# Sec_Controller_Sheet1.net
KiCad netlist of a schematic drawn in Altium Designer
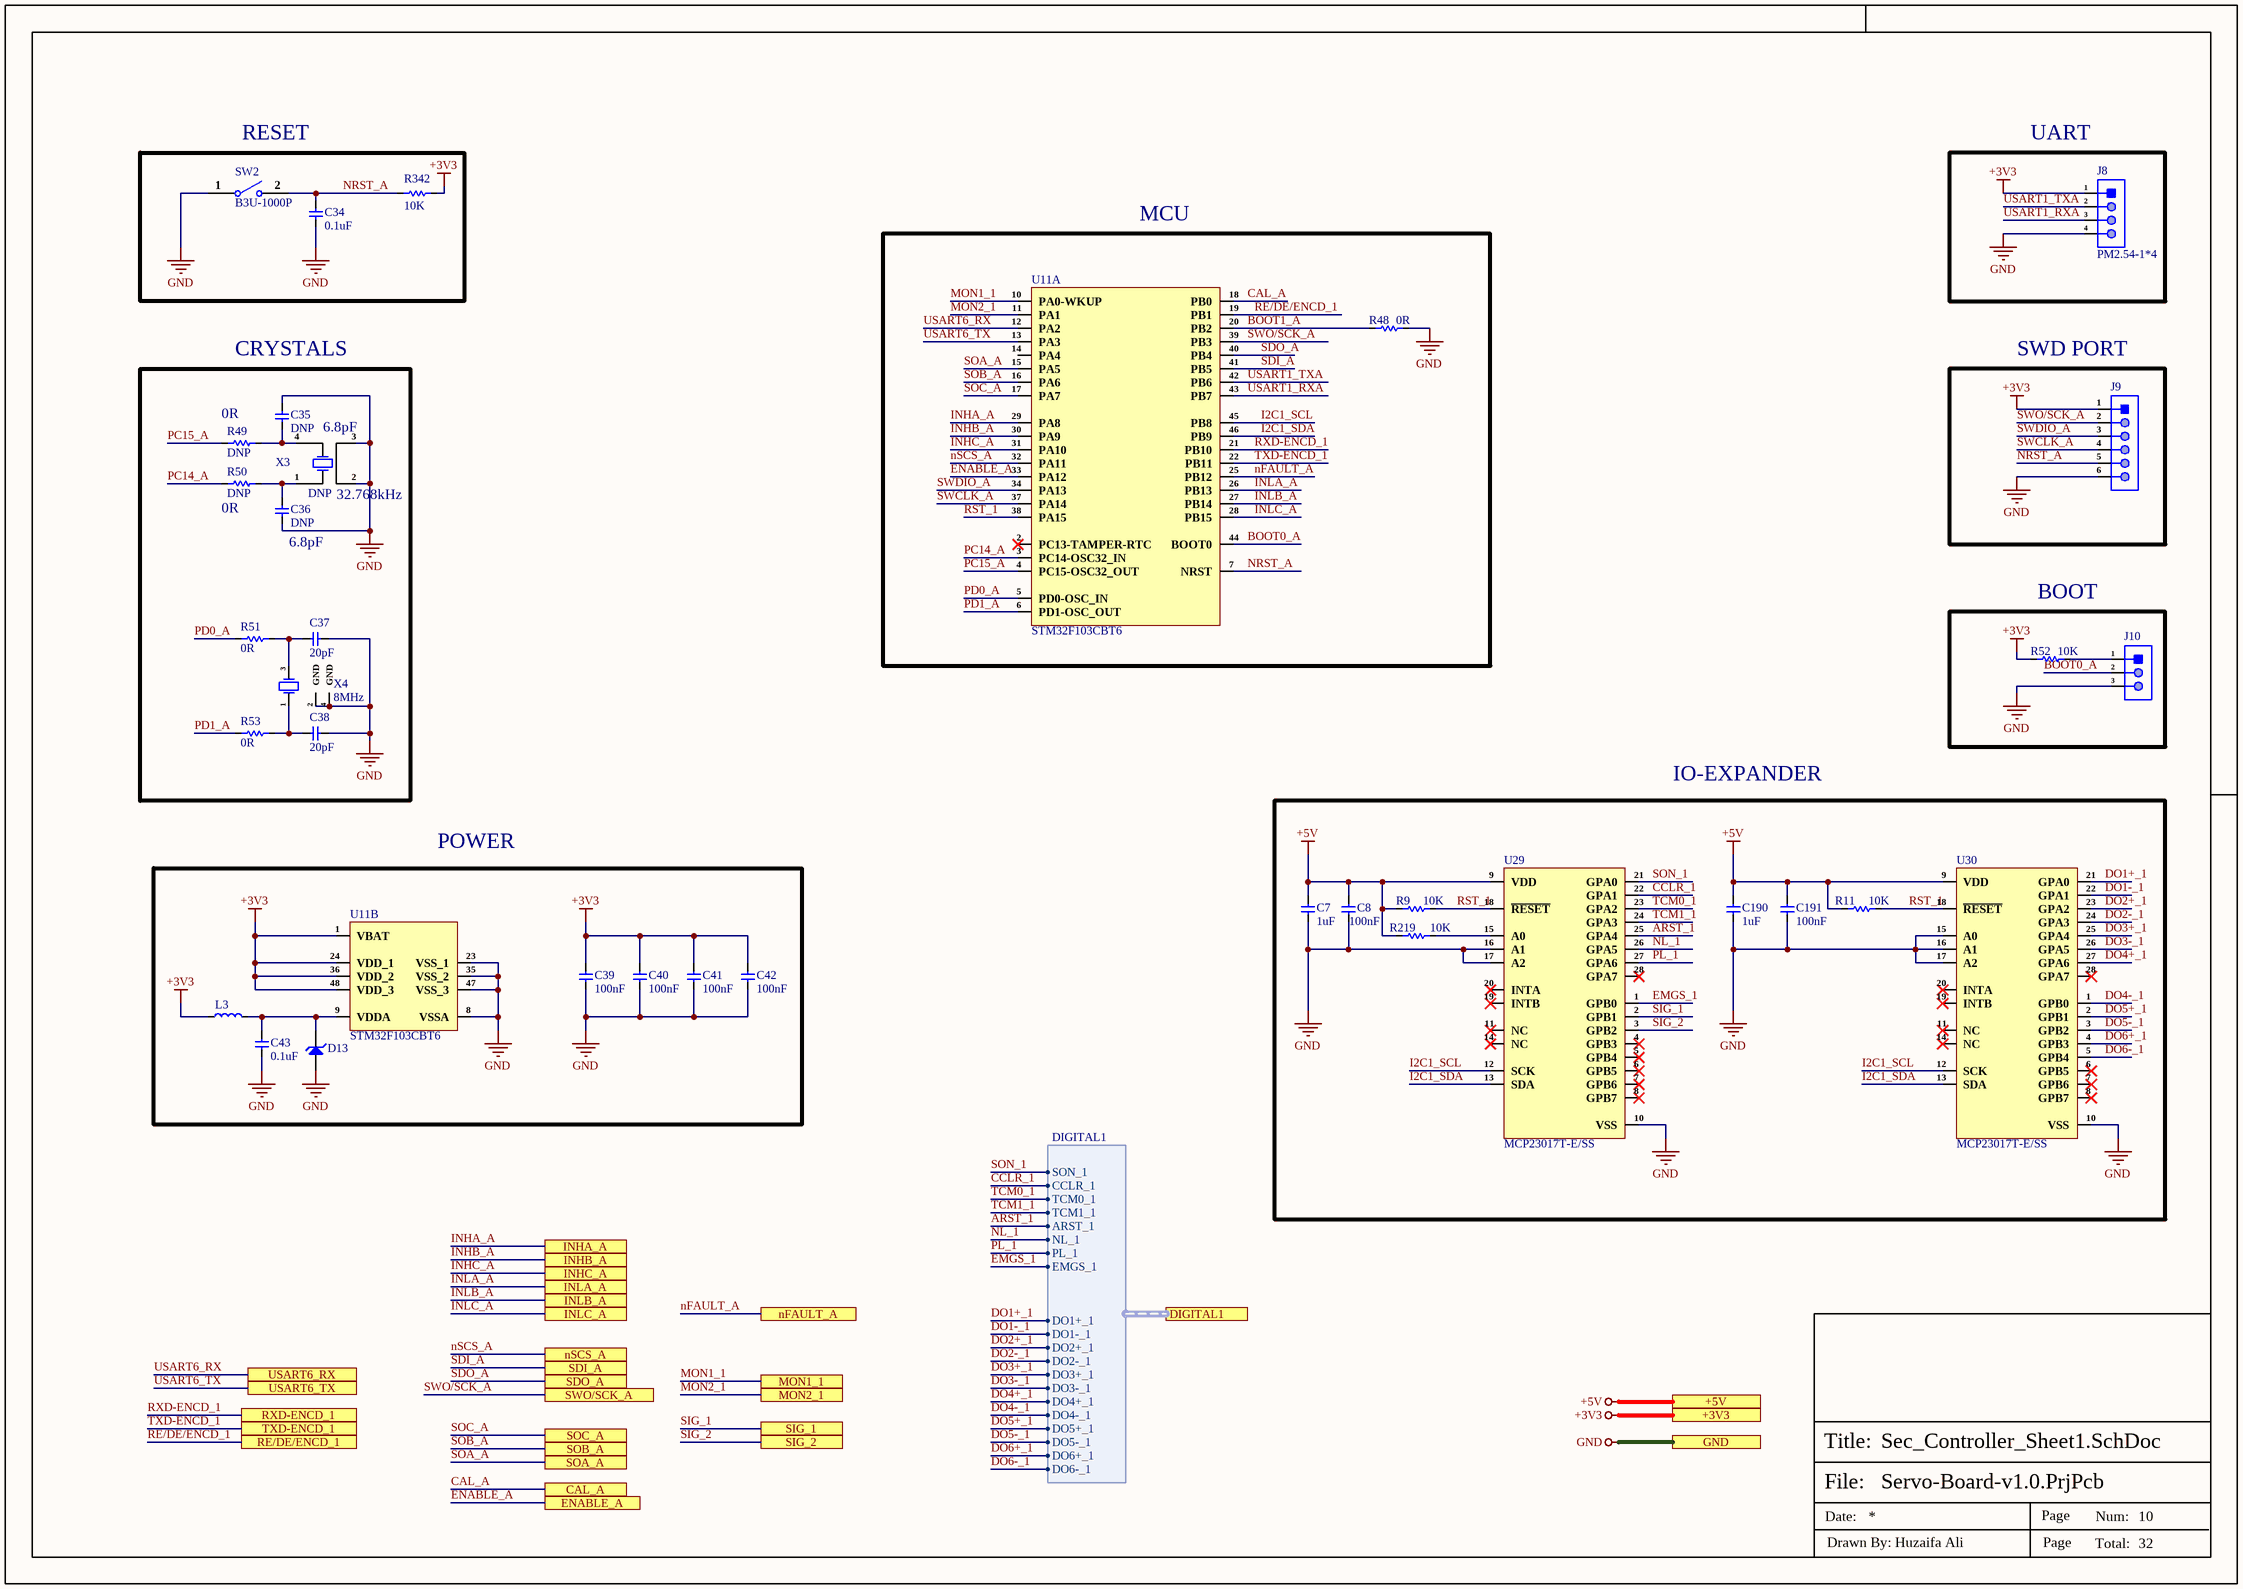
[diagram p0: Sec_Controller_Sheet1.SchDoc]

(export (version "E")
  (design (tool "Eeschema 10.0.6"))
  (components
    (comp (ref "C7")
      (value "1uF")
      (footprint "Cap-0402")
      (description "CAP CER 1UF 10V X5R 0402")
      (fields
        (field (name "MANUFACTURER") "Yageo")
        (field (name "MANUFACTURER PART NUMBER") "CC0402KRX5R6BB105")
      )
      (libsource (lib "eSpark Libraries") (part "CC0402KRX5R6BB105"))
    )
    (comp (ref "C8")
      (value "100nF")
      (footprint "cap-0402")
      (description "CAP CER 0.1UF 50V X7R 0402")
      (fields
        (field (name "MANUFACTURER") "TDK")
        (field (name "MANUFACTURER PART NUMBER") "C1005X7R1H104KT000F")
      )
      (libsource (lib "eSpark Libraries") (part "C1005X7R1H104KT000F"))
    )
    (comp (ref "C34")
      (value "0.1uF")
      (footprint "Cap-0402")
      (description "CAP CER 0.1UF 16V X7R 0402")
      (fields
        (field (name "MANUFACTURER") "Yageo")
        (field (name "MANUFACTURER PART NUMBER") "CC0402JRX7R7BB104")
      )
      (libsource (lib "eSpark Libraries") (part "CC0402JRX7R7BB104"))
    )
    (comp (ref "C35")
      (value "DNP")
      (footprint "Cap-0402")
      (description "CAP CER 6.8PF 50V C0G/NPO 0402")
      (fields
        (field (name "MANUFACTURER") "Yageo")
        (field (name "MANUFACTURER PART NUMBER") "CC0402CRNPO9BN6R8")
      )
      (libsource (lib "eSpark Libraries") (part "CC0402CRNPO9BN6R8"))
    )
    (comp (ref "C36")
      (value "DNP")
      (footprint "Cap-0402")
      (description "CAP CER 6.8PF 50V C0G/NPO 0402")
      (fields
        (field (name "MANUFACTURER") "Yageo")
        (field (name "MANUFACTURER PART NUMBER") "CC0402CRNPO9BN6R8")
      )
      (libsource (lib "eSpark Libraries") (part "CC0402CRNPO9BN6R8"))
    )
    (comp (ref "C37")
      (value "20pF")
      (footprint "Cap-0402")
      (description "CAP CER 20PF 50V C0G/NPO 0402")
      (fields (field (name "LCSC PART NUMBER") "C107000") (field (name "MANUFACTURER") "Yageo"))
      (libsource (lib "eSpark Libraries") (part "CC0402JRNPO9BN200"))
    )
    (comp (ref "C38")
      (value "20pF")
      (footprint "Cap-0402")
      (description "CAP CER 20PF 50V C0G/NPO 0402")
      (fields (field (name "LCSC PART NUMBER") "C107000") (field (name "MANUFACTURER") "Yageo"))
      (libsource (lib "eSpark Libraries") (part "CC0402JRNPO9BN200"))
    )
    (comp (ref "C39")
      (value "100nF")
      (footprint "cap-0402")
      (description "CAP CER 0.1UF 50V X7R 0402")
      (fields
        (field (name "MANUFACTURER") "TDK")
        (field (name "MANUFACTURER PART NUMBER") "C1005X7R1H104KT000F")
      )
      (libsource (lib "eSpark Libraries") (part "C1005X7R1H104KT000F"))
    )
    (comp (ref "C40")
      (value "100nF")
      (footprint "cap-0402")
      (description "CAP CER 0.1UF 50V X7R 0402")
      (fields
        (field (name "MANUFACTURER") "TDK")
        (field (name "MANUFACTURER PART NUMBER") "C1005X7R1H104KT000F")
      )
      (libsource (lib "eSpark Libraries") (part "C1005X7R1H104KT000F"))
    )
    (comp (ref "C41")
      (value "100nF")
      (footprint "cap-0402")
      (description "CAP CER 0.1UF 50V X7R 0402")
      (fields
        (field (name "MANUFACTURER") "TDK")
        (field (name "MANUFACTURER PART NUMBER") "C1005X7R1H104KT000F")
      )
      (libsource (lib "eSpark Libraries") (part "C1005X7R1H104KT000F"))
    )
    (comp (ref "C42")
      (value "100nF")
      (footprint "cap-0402")
      (description "CAP CER 0.1UF 50V X7R 0402")
      (fields
        (field (name "MANUFACTURER") "TDK")
        (field (name "MANUFACTURER PART NUMBER") "C1005X7R1H104KT000F")
      )
      (libsource (lib "eSpark Libraries") (part "C1005X7R1H104KT000F"))
    )
    (comp (ref "C43")
      (value "0.1uF")
      (footprint "Cap-0402")
      (description "CAP CER 0.1UF 16V X7R 0402")
      (fields
        (field (name "MANUFACTURER") "Yageo")
        (field (name "MANUFACTURER PART NUMBER") "CC0402JRX7R7BB104")
      )
      (libsource (lib "eSpark Libraries") (part "CC0402JRX7R7BB104"))
    )
    (comp (ref "C190")
      (value "1uF")
      (footprint "Cap-0402")
      (description "CAP CER 1UF 10V X5R 0402")
      (fields
        (field (name "MANUFACTURER") "Yageo")
        (field (name "MANUFACTURER PART NUMBER") "CC0402KRX5R6BB105")
      )
      (libsource (lib "eSpark Libraries") (part "CC0402KRX5R6BB105"))
    )
    (comp (ref "C191")
      (value "100nF")
      (footprint "cap-0402")
      (description "CAP CER 0.1UF 50V X7R 0402")
      (fields
        (field (name "MANUFACTURER") "TDK")
        (field (name "MANUFACTURER PART NUMBER") "C1005X7R1H104KT000F")
      )
      (libsource (lib "eSpark Libraries") (part "C1005X7R1H104KT000F"))
    )
    (comp (ref "D13")
      (value "AZ3003-01G")
      (footprint "SOD-123")
      (description "TVS SURGE PROTECTOR 1-CH 3.3V")
      (fields (field (name "MANUFACTURER") "Amazing"))
      (libsource (lib "eSpark Libraries") (part "AZ3003-01G"))
    )
    (comp (ref "J8")
      (value "PM2.54-1*4")
      (footprint "HDR1X4 Female")
      (fields (field (name "MANUFACTURER") "ZHOURI") (field (name "LCSC PART NUMBER") "C5116530"))
      (libsource (lib "eSpark Libraries") (part "PM2.54-1*4"))
    )
    (comp (ref "J9")
      (value "X6511WV-06H-C60D30")
      (footprint "HDR1X6_")
      (fields (field (name "MANUFACTURER") "XKB") (field (name "LCSC PART NUMBER") "C706878"))
      (libsource (lib "eSpark Libraries") (part "X6511WV-06H-C60D30"))
    )
    (comp (ref "J10")
      (value "68000-103HLF")
      (footprint "HDR1X3_")
      (description "CONN HEADER VERT 3POS 2.54MM")
      (fields (field (name "LCSC PART NUMBER") "C168677"))
      (libsource (lib "eSpark Libraries") (part "68000-103HLF"))
    )
    (comp (ref "L3")
      (value "BLM15AG601SN1D")
      (footprint "IND-0402")
      (description "FERRITE BEAD 600 OHM 0402 1LN")
      (fields (field (name "MANUFACTURER") "Murata") (field (name "TOLERANCE") "25%"))
      (libsource (lib "eSpark Libraries") (part "BLM15AG601SN1D"))
    )
    (comp (ref "R9")
      (value "10K")
      (footprint "Res-0402")
      (description "RES 10K OHM 1% 1/16W 0402")
      (fields
        (field (name "MANUFACTURER") "Yageo")
        (field (name "MANUFACTURER PART NUMBER") "RC0402FR-0710KL")
      )
      (libsource (lib "eSpark Libraries") (part "RC0402FR-0710KL"))
    )
    (comp (ref "R11")
      (value "10K")
      (footprint "Res-0402")
      (description "RES 10K OHM 1% 1/16W 0402")
      (fields
        (field (name "MANUFACTURER") "Yageo")
        (field (name "MANUFACTURER PART NUMBER") "RC0402FR-0710KL")
      )
      (libsource (lib "eSpark Libraries") (part "RC0402FR-0710KL"))
    )
    (comp (ref "R48")
      (value "0R")
      (footprint "Res-0402")
      (description "RES 0 OHM JUMPER 1/16W 0402")
      (fields
        (field (name "MANUFACTURER") "Yageo")
        (field (name "MANUFACTURER PART NUMBER") "RC0402FR-070RL")
      )
      (libsource (lib "eSpark Libraries") (part "RC0402FR-070RL"))
    )
    (comp (ref "R49")
      (value "DNP")
      (footprint "Res-0603")
      (description "RES 0 OHM JUMPER 1/10W 0603")
      (fields
        (field (name "MANUFACTURER") "Yageo")
        (field (name "MANUFACTURER PART NUMBER") "RC0603JR-070RL")
      )
      (libsource (lib "eSpark Libraries") (part "RC0603JR-070RL"))
    )
    (comp (ref "R50")
      (value "DNP")
      (footprint "Res-0603")
      (description "RES 0 OHM JUMPER 1/10W 0603")
      (fields
        (field (name "MANUFACTURER") "Yageo")
        (field (name "MANUFACTURER PART NUMBER") "RC0603JR-070RL")
      )
      (libsource (lib "eSpark Libraries") (part "RC0603JR-070RL"))
    )
    (comp (ref "R51")
      (value "0R")
      (footprint "Res-0603")
      (description "RES 0 OHM JUMPER 1/10W 0603")
      (fields
        (field (name "MANUFACTURER") "Yageo")
        (field (name "MANUFACTURER PART NUMBER") "RC0603JR-070RL")
      )
      (libsource (lib "eSpark Libraries") (part "RC0603JR-070RL"))
    )
    (comp (ref "R52")
      (value "10K")
      (footprint "Res-0402")
      (description "RES 10K OHM 1% 1/16W 0402")
      (fields
        (field (name "MANUFACTURER") "Yageo")
        (field (name "MANUFACTURER PART NUMBER") "RC0402FR-0710KL")
      )
      (libsource (lib "eSpark Libraries") (part "RC0402FR-0710KL"))
    )
    (comp (ref "R53")
      (value "0R")
      (footprint "Res-0603")
      (description "RES 0 OHM JUMPER 1/10W 0603")
      (fields
        (field (name "MANUFACTURER") "Yageo")
        (field (name "MANUFACTURER PART NUMBER") "RC0603JR-070RL")
      )
      (libsource (lib "eSpark Libraries") (part "RC0603JR-070RL"))
    )
    (comp (ref "R219")
      (value "10K")
      (footprint "Res-0402")
      (description "RES 10K OHM 1% 1/16W 0402")
      (fields
        (field (name "MANUFACTURER") "Yageo")
        (field (name "MANUFACTURER PART NUMBER") "RC0402FR-0710KL")
      )
      (libsource (lib "eSpark Libraries") (part "RC0402FR-0710KL"))
    )
    (comp (ref "R342")
      (value "10K")
      (footprint "Res-0402")
      (description "RES 10K OHM 1% 1/16W 0402")
      (fields
        (field (name "MANUFACTURER") "Yageo")
        (field (name "MANUFACTURER PART NUMBER") "RC0402FR-0710KL")
      )
      (libsource (lib "eSpark Libraries") (part "RC0402FR-0710KL"))
    )
    (comp (ref "SW2")
      (value "B3U-1000P")
      (footprint "B3U-1000P")
      (description "SWITCH TACTILE SPST-NO 0.05A 12V")
      (fields (field (name "MANUFACTURER") "Omron") (field (name "LCSC PART NUMBER") "C231329"))
      (libsource (lib "eSpark Libraries") (part "B3U-1000P"))
    )
    (comp (ref "U11")
      (value "STM32F103CBT6")
      (footprint "48-LQFP (7x7)_")
      (description "IC MCU 32BIT 128KB FLASH 48LQFP")
      (fields (field (name "MANUFACTURER") "STMicroelectronics") (field (name "LCSC PART NUMBER") "C8304"))
      (libsource (lib "eSpark Libraries") (part "STM32F103CBT6"))
    )
    (comp (ref "U29")
      (value "MCP23017T-E/SS")
      (footprint "SSOP-28-208mil")
      (description "IC XPNDR 1.7MHZ I2C 28SSOP")
      (fields (field (name "MANUFACTURER") "Microchip") (field (name "LCSC PART NUMBER") "C558584"))
      (libsource (lib "eSpark Libraries") (part "MCP23017T-E/SS"))
    )
    (comp (ref "U30")
      (value "MCP23017T-E/SS")
      (footprint "SSOP-28-208mil")
      (description "IC XPNDR 1.7MHZ I2C 28SSOP")
      (fields (field (name "MANUFACTURER") "Microchip") (field (name "LCSC PART NUMBER") "C558584"))
      (libsource (lib "eSpark Libraries") (part "MCP23017T-E/SS"))
    )
    (comp (ref "X3")
      (value "DNP")
      (footprint "MC-306")
      (description "32.768kHz 12.5pF ±20ppm MC-306 Crystals ROHS")
      (fields
        (field (name "MANUFACTURER") "Seiko Epson")
        (field (name "MANUFACTURER PART NUMBER") "MC-306 32.7680K-A0:ROHS")
      )
      (libsource (lib "eSpark Libraries") (part "MC-306 32.7680K-A0{colon}ROHS"))
    )
    (comp (ref "X4")
      (value "8MHz")
      (footprint "5TJ480000XYLBC_")
      (description "8MHz 18pF ±10ppm SMD5032-4P Crystals ROHS")
      (fields (field (name "MANUFACTURER") "JYJE") (field (name "MANUFACTURER PART NUMBER") "5TJ480000XYLBC"))
      (libsource (lib "eSpark Libraries") (part "5TJ480000XYLBC"))
    )
  )
  (nets
    (net (code "2") (name "+3V3") (class "Default")
      (node (ref "C39") (pin "2") (pinfunction "2_2") (pintype "passive"))
      (node (ref "C40") (pin "2") (pinfunction "2_2") (pintype "passive"))
      (node (ref "C41") (pin "2") (pinfunction "2_2") (pintype "passive"))
      (node (ref "C42") (pin "2") (pinfunction "2_2") (pintype "passive"))
      (node (ref "J8") (pin "1") (pinfunction "1_1") (pintype "passive"))
      (node (ref "J9") (pin "1") (pinfunction "1_1") (pintype "passive"))
      (node (ref "L3") (pin "1") (pinfunction "1_1") (pintype "passive"))
      (node (ref "R342") (pin "2") (pinfunction "2_2") (pintype "passive"))
      (node (ref "R52") (pin "2") (pinfunction "2_2") (pintype "passive"))
      (node (ref "U11") (pin "1") (pinfunction "VBAT_1") (pintype "power_in"))
      (node (ref "U11") (pin "24") (pinfunction "VDD_1_24") (pintype "power_in"))
      (node (ref "U11") (pin "36") (pinfunction "VDD_2_36") (pintype "power_in"))
      (node (ref "U11") (pin "48") (pinfunction "VDD_3_48") (pintype "power_in"))
    )
    (net (code "3") (name "+5V") (class "Default")
      (node (ref "C190") (pin "2") (pinfunction "2_2") (pintype "passive"))
      (node (ref "C191") (pin "2") (pinfunction "2_2") (pintype "passive"))
      (node (ref "C7") (pin "2") (pinfunction "2_2") (pintype "passive"))
      (node (ref "C8") (pin "2") (pinfunction "2_2") (pintype "passive"))
      (node (ref "R11") (pin "2") (pinfunction "2_2") (pintype "passive"))
      (node (ref "R219") (pin "2") (pinfunction "2_2") (pintype "passive"))
      (node (ref "R9") (pin "2") (pinfunction "2_2") (pintype "passive"))
      (node (ref "U29") (pin "9") (pinfunction "VDD_9") (pintype "passive"))
      (node (ref "U30") (pin "9") (pinfunction "VDD_9") (pintype "passive"))
    )
    (net (code "4") (name "/ARST_1") (class "Default")
      (node (ref "U29") (pin "25") (pinfunction "GPA4_25") (pintype "passive"))
    )
    (net (code "5") (name "/BOOT0_A") (class "Default")
      (node (ref "J10") (pin "2") (pinfunction "2_2") (pintype "passive"))
      (node (ref "U11") (pin "44") (pinfunction "BOOT0_44") (pintype "passive"))
    )
    (net (code "6") (name "/BOOT1_A") (class "Default")
      (node (ref "R48") (pin "1") (pinfunction "1_1") (pintype "passive"))
      (node (ref "U11") (pin "20") (pinfunction "PB2_20") (pintype "passive"))
    )
    (net (code "7") (name "/CAL_A") (class "Default")
      (node (ref "U11") (pin "18") (pinfunction "PB0_18") (pintype "passive"))
    )
    (net (code "8") (name "/CCLR_1") (class "Default")
      (node (ref "U29") (pin "22") (pinfunction "GPA1_22") (pintype "passive"))
    )
    (net (code "9") (name "/DO1+_1") (class "Default")
      (node (ref "U30") (pin "21") (pinfunction "GPA0_21") (pintype "passive"))
    )
    (net (code "10") (name "/DO1-_1") (class "Default")
      (node (ref "U30") (pin "22") (pinfunction "GPA1_22") (pintype "passive"))
    )
    (net (code "11") (name "/DO2+_1") (class "Default")
      (node (ref "U30") (pin "23") (pinfunction "GPA2_23") (pintype "passive"))
    )
    (net (code "12") (name "/DO2-_1") (class "Default")
      (node (ref "U30") (pin "24") (pinfunction "GPA3_24") (pintype "passive"))
    )
    (net (code "13") (name "/DO3+_1") (class "Default")
      (node (ref "U30") (pin "25") (pinfunction "GPA4_25") (pintype "passive"))
    )
    (net (code "14") (name "/DO3-_1") (class "Default")
      (node (ref "U30") (pin "26") (pinfunction "GPA5_26") (pintype "passive"))
    )
    (net (code "15") (name "/DO4+_1") (class "Default")
      (node (ref "U30") (pin "27") (pinfunction "GPA6_27") (pintype "passive"))
    )
    (net (code "16") (name "/DO4-_1") (class "Default")
      (node (ref "U30") (pin "1") (pinfunction "GPB0_1") (pintype "passive"))
    )
    (net (code "17") (name "/DO5+_1") (class "Default")
      (node (ref "U30") (pin "2") (pinfunction "GPB1_2") (pintype "passive"))
    )
    (net (code "18") (name "/DO5-_1") (class "Default")
      (node (ref "U30") (pin "3") (pinfunction "GPB2_3") (pintype "passive"))
    )
    (net (code "19") (name "/DO6+_1") (class "Default")
      (node (ref "U30") (pin "4") (pinfunction "GPB3_4") (pintype "passive"))
    )
    (net (code "20") (name "/DO6-_1") (class "Default")
      (node (ref "U30") (pin "5") (pinfunction "GPB4_5") (pintype "passive"))
    )
    (net (code "21") (name "/EMGS_1") (class "Default")
      (node (ref "U29") (pin "1") (pinfunction "GPB0_1") (pintype "passive"))
    )
    (net (code "22") (name "/ENABLE_A") (class "Default")
      (node (ref "U11") (pin "33") (pinfunction "PA12_33") (pintype "passive"))
    )
    (net (code "23") (name "/I2C1_SCL") (class "Default")
      (node (ref "U11") (pin "45") (pinfunction "PB8_45") (pintype "passive"))
      (node (ref "U29") (pin "12") (pinfunction "SCK_12") (pintype "passive"))
      (node (ref "U30") (pin "12") (pinfunction "SCK_12") (pintype "passive"))
    )
    (net (code "24") (name "/I2C1_SDA") (class "Default")
      (node (ref "U11") (pin "46") (pinfunction "PB9_46") (pintype "passive"))
      (node (ref "U29") (pin "13") (pinfunction "SDA_13") (pintype "passive"))
      (node (ref "U30") (pin "13") (pinfunction "SDA_13") (pintype "passive"))
    )
    (net (code "25") (name "/INHA_A") (class "Default")
      (node (ref "U11") (pin "29") (pinfunction "PA8_29") (pintype "passive"))
    )
    (net (code "26") (name "/INHB_A") (class "Default")
      (node (ref "U11") (pin "30") (pinfunction "PA9_30") (pintype "passive"))
    )
    (net (code "27") (name "/INHC_A") (class "Default")
      (node (ref "U11") (pin "31") (pinfunction "PA10_31") (pintype "passive"))
    )
    (net (code "28") (name "/INLA_A") (class "Default")
      (node (ref "U11") (pin "26") (pinfunction "PB13_26") (pintype "passive"))
    )
    (net (code "29") (name "/INLB_A") (class "Default")
      (node (ref "U11") (pin "27") (pinfunction "PB14_27") (pintype "passive"))
    )
    (net (code "30") (name "/INLC_A") (class "Default")
      (node (ref "U11") (pin "28") (pinfunction "PB15_28") (pintype "passive"))
    )
    (net (code "31") (name "/MON1_1") (class "Default")
      (node (ref "U11") (pin "10") (pinfunction "PA0-WKUP_10") (pintype "passive"))
    )
    (net (code "32") (name "/MON2_1") (class "Default")
      (node (ref "U11") (pin "11") (pinfunction "PA1_11") (pintype "passive"))
    )
    (net (code "33") (name "/NL_1") (class "Default")
      (node (ref "U29") (pin "26") (pinfunction "GPA5_26") (pintype "passive"))
    )
    (net (code "34") (name "/NRST_A") (class "Default")
      (node (ref "C34") (pin "2") (pinfunction "2_2") (pintype "passive"))
      (node (ref "J9") (pin "5") (pinfunction "5_5") (pintype "passive"))
      (node (ref "R342") (pin "1") (pinfunction "1_1") (pintype "passive"))
      (node (ref "SW2") (pin "2") (pinfunction "2_2") (pintype "passive"))
      (node (ref "U11") (pin "7") (pinfunction "NRST_7") (pintype "passive"))
    )
    (net (code "35") (name "/PC14_A") (class "Default")
      (node (ref "R50") (pin "2") (pinfunction "2_2") (pintype "passive"))
      (node (ref "U11") (pin "3") (pinfunction "PC14-OSC32_IN_3") (pintype "passive"))
    )
    (net (code "36") (name "/PC15_A") (class "Default")
      (node (ref "R49") (pin "2") (pinfunction "2_2") (pintype "passive"))
      (node (ref "U11") (pin "4") (pinfunction "PC15-OSC32_OUT_4") (pintype "passive"))
    )
    (net (code "37") (name "/PD0_A") (class "Default")
      (node (ref "R51") (pin "2") (pinfunction "2_2") (pintype "passive"))
      (node (ref "U11") (pin "5") (pinfunction "PD0-OSC_IN_5") (pintype "passive"))
    )
    (net (code "38") (name "/PD1_A") (class "Default")
      (node (ref "R53") (pin "2") (pinfunction "2_2") (pintype "passive"))
      (node (ref "U11") (pin "6") (pinfunction "PD1-OSC_OUT_6") (pintype "passive"))
    )
    (net (code "39") (name "/PL_1") (class "Default")
      (node (ref "U29") (pin "27") (pinfunction "GPA6_27") (pintype "passive"))
    )
    (net (code "40") (name "/RE{slash}DE{slash}ENCD_1") (class "Default")
      (node (ref "U11") (pin "19") (pinfunction "PB1_19") (pintype "passive"))
    )
    (net (code "41") (name "/RST_1") (class "Default")
      (node (ref "R11") (pin "1") (pinfunction "1_1") (pintype "passive"))
      (node (ref "R9") (pin "1") (pinfunction "1_1") (pintype "passive"))
      (node (ref "U11") (pin "38") (pinfunction "PA15_38") (pintype "passive"))
      (node (ref "U29") (pin "18") (pinfunction "~{RESET}_18") (pintype "passive"))
      (node (ref "U30") (pin "18") (pinfunction "~{RESET}_18") (pintype "passive"))
    )
    (net (code "42") (name "/RXD-ENCD_1") (class "Default")
      (node (ref "U11") (pin "21") (pinfunction "PB10_21") (pintype "passive"))
    )
    (net (code "43") (name "/SDI_A") (class "Default")
      (node (ref "U11") (pin "41") (pinfunction "PB5_41") (pintype "passive"))
    )
    (net (code "44") (name "/SDO_A") (class "Default")
      (node (ref "U11") (pin "40") (pinfunction "PB4_40") (pintype "passive"))
    )
    (net (code "45") (name "/SIG_1") (class "Default")
      (node (ref "U29") (pin "2") (pinfunction "GPB1_2") (pintype "passive"))
    )
    (net (code "46") (name "/SIG_2") (class "Default")
      (node (ref "U29") (pin "3") (pinfunction "GPB2_3") (pintype "passive"))
    )
    (net (code "47") (name "/SOA_A") (class "Default")
      (node (ref "U11") (pin "15") (pinfunction "PA5_15") (pintype "passive"))
    )
    (net (code "48") (name "/SOB_A") (class "Default")
      (node (ref "U11") (pin "16") (pinfunction "PA6_16") (pintype "passive"))
    )
    (net (code "49") (name "/SOC_A") (class "Default")
      (node (ref "U11") (pin "17") (pinfunction "PA7_17") (pintype "passive"))
    )
    (net (code "50") (name "/SON_1") (class "Default")
      (node (ref "U29") (pin "21") (pinfunction "GPA0_21") (pintype "passive"))
    )
    (net (code "51") (name "/SWCLK_A") (class "Default")
      (node (ref "J9") (pin "4") (pinfunction "4_4") (pintype "passive"))
      (node (ref "U11") (pin "37") (pinfunction "PA14_37") (pintype "passive"))
    )
    (net (code "52") (name "/SWDIO_A") (class "Default")
      (node (ref "J9") (pin "3") (pinfunction "3_3") (pintype "passive"))
      (node (ref "U11") (pin "34") (pinfunction "PA13_34") (pintype "passive"))
    )
    (net (code "53") (name "/SWO{slash}SCK_A") (class "Default")
      (node (ref "J9") (pin "2") (pinfunction "2_2") (pintype "passive"))
      (node (ref "U11") (pin "39") (pinfunction "PB3_39") (pintype "passive"))
    )
    (net (code "54") (name "/TCM0_1") (class "Default")
      (node (ref "U29") (pin "23") (pinfunction "GPA2_23") (pintype "passive"))
    )
    (net (code "55") (name "/TCM1_1") (class "Default")
      (node (ref "U29") (pin "24") (pinfunction "GPA3_24") (pintype "passive"))
    )
    (net (code "56") (name "/TXD-ENCD_1") (class "Default")
      (node (ref "U11") (pin "22") (pinfunction "PB11_22") (pintype "passive"))
    )
    (net (code "57") (name "/USART1_RXA") (class "Default")
      (node (ref "J8") (pin "3") (pinfunction "3_3") (pintype "passive"))
      (node (ref "U11") (pin "43") (pinfunction "PB7_43") (pintype "passive"))
    )
    (net (code "58") (name "/USART1_TXA") (class "Default")
      (node (ref "J8") (pin "2") (pinfunction "2_2") (pintype "passive"))
      (node (ref "U11") (pin "42") (pinfunction "PB6_42") (pintype "passive"))
    )
    (net (code "59") (name "/USART6_RX") (class "Default")
      (node (ref "U11") (pin "12") (pinfunction "PA2_12") (pintype "passive"))
    )
    (net (code "60") (name "/USART6_TX") (class "Default")
      (node (ref "U11") (pin "13") (pinfunction "PA3_13") (pintype "passive"))
    )
    (net (code "61") (name "/nFAULT_A") (class "Default")
      (node (ref "U11") (pin "25") (pinfunction "PB12_25") (pintype "passive"))
    )
    (net (code "62") (name "/nSCS_A") (class "Default")
      (node (ref "U11") (pin "32") (pinfunction "PA11_32") (pintype "passive"))
    )
    (net (code "64") (name "GND") (class "Default")
      (node (ref "C190") (pin "1") (pinfunction "1_1") (pintype "passive"))
      (node (ref "C191") (pin "1") (pinfunction "1_1") (pintype "passive"))
      (node (ref "C34") (pin "1") (pinfunction "1_1") (pintype "passive"))
      (node (ref "C35") (pin "2") (pinfunction "2_2") (pintype "passive"))
      (node (ref "C36") (pin "1") (pinfunction "1_1") (pintype "passive"))
      (node (ref "C37") (pin "2") (pinfunction "2_2") (pintype "passive"))
      (node (ref "C38") (pin "2") (pinfunction "2_2") (pintype "passive"))
      (node (ref "C39") (pin "1") (pinfunction "1_1") (pintype "passive"))
      (node (ref "C40") (pin "1") (pinfunction "1_1") (pintype "passive"))
      (node (ref "C41") (pin "1") (pinfunction "1_1") (pintype "passive"))
      (node (ref "C42") (pin "1") (pinfunction "1_1") (pintype "passive"))
      (node (ref "C43") (pin "1") (pinfunction "1_1") (pintype "passive"))
      (node (ref "C7") (pin "1") (pinfunction "1_1") (pintype "passive"))
      (node (ref "C8") (pin "1") (pinfunction "1_1") (pintype "passive"))
      (node (ref "D13") (pin "1") (pinfunction "A_1") (pintype "passive"))
      (node (ref "J10") (pin "3") (pinfunction "3_3") (pintype "passive"))
      (node (ref "J8") (pin "4") (pinfunction "4_4") (pintype "passive"))
      (node (ref "J9") (pin "6") (pinfunction "6_6") (pintype "passive"))
      (node (ref "R48") (pin "2") (pinfunction "2_2") (pintype "passive"))
      (node (ref "SW2") (pin "1") (pinfunction "1_1") (pintype "passive"))
      (node (ref "U11") (pin "23") (pinfunction "VSS_1_23") (pintype "power_in"))
      (node (ref "U11") (pin "35") (pinfunction "VSS_2_35") (pintype "power_in"))
      (node (ref "U11") (pin "47") (pinfunction "VSS_3_47") (pintype "power_in"))
      (node (ref "U11") (pin "8") (pinfunction "VSSA_8") (pintype "power_in"))
      (node (ref "U29") (pin "10") (pinfunction "VSS_10") (pintype "passive"))
      (node (ref "U29") (pin "16") (pinfunction "A1_16") (pintype "passive"))
      (node (ref "U29") (pin "17") (pinfunction "A2_17") (pintype "passive"))
      (node (ref "U30") (pin "10") (pinfunction "VSS_10") (pintype "passive"))
      (node (ref "U30") (pin "15") (pinfunction "A0_15") (pintype "passive"))
      (node (ref "U30") (pin "16") (pinfunction "A1_16") (pintype "passive"))
      (node (ref "U30") (pin "17") (pinfunction "A2_17") (pintype "passive"))
      (node (ref "X3") (pin "2") (pinfunction "2_2") (pintype "passive"))
      (node (ref "X3") (pin "3") (pinfunction "3_3") (pintype "passive"))
      (node (ref "X4") (pin "2") (pinfunction "GND_2") (pintype "passive"))
      (node (ref "X4") (pin "4") (pinfunction "GND_4") (pintype "passive"))
    )
    (net (code "65") (name "Net-(D13-K)") (class "Default")
      (node (ref "C43") (pin "2") (pinfunction "2_2") (pintype "passive"))
      (node (ref "D13") (pin "2") (pinfunction "K_2") (pintype "passive"))
      (node (ref "L3") (pin "2") (pinfunction "2_2") (pintype "passive"))
      (node (ref "U11") (pin "9") (pinfunction "VDDA_9") (pintype "power_in"))
    )
    (net (code "66") (name "Net-(J10-Pad1)") (class "Default")
      (node (ref "J10") (pin "1") (pinfunction "1_1") (pintype "passive"))
      (node (ref "R52") (pin "1") (pinfunction "1_1") (pintype "passive"))
    )
    (net (code "67") (name "Net-(U29-A0)") (class "Default")
      (node (ref "R219") (pin "1") (pinfunction "1_1") (pintype "passive"))
      (node (ref "U29") (pin "15") (pinfunction "A0_15") (pintype "passive"))
    )
    (net (code "68") (name "Net-(X3-OSC1)") (class "Default")
      (node (ref "C36") (pin "2") (pinfunction "2_2") (pintype "passive"))
      (node (ref "R50") (pin "1") (pinfunction "1_1") (pintype "passive"))
      (node (ref "X3") (pin "1") (pinfunction "OSC1_1") (pintype "passive"))
    )
    (net (code "69") (name "Net-(X3-OSC2)") (class "Default")
      (node (ref "C35") (pin "1") (pinfunction "1_1") (pintype "passive"))
      (node (ref "R49") (pin "1") (pinfunction "1_1") (pintype "passive"))
      (node (ref "X3") (pin "4") (pinfunction "OSC2_4") (pintype "passive"))
    )
    (net (code "70") (name "Net-(X4-OSC1)") (class "Default")
      (node (ref "C38") (pin "1") (pinfunction "1_1") (pintype "passive"))
      (node (ref "R53") (pin "1") (pinfunction "1_1") (pintype "passive"))
      (node (ref "X4") (pin "1") (pinfunction "OSC1_1") (pintype "passive"))
    )
    (net (code "71") (name "Net-(X4-OSC2)") (class "Default")
      (node (ref "C37") (pin "1") (pinfunction "1_1") (pintype "passive"))
      (node (ref "R51") (pin "1") (pinfunction "1_1") (pintype "passive"))
      (node (ref "X4") (pin "3") (pinfunction "OSC2_3") (pintype "passive"))
    )
    (net (code "72") (name "unconnected-(U11A-PA4-Pad14)") (class "Default")
      (node (ref "U11") (pin "14") (pinfunction "PA4_14") (pintype "passive"))
    )
    (net (code "73") (name "unconnected-(U11A-PC13-TAMPER-RTC-Pad2)") (class "Default")
      (node (ref "U11") (pin "2") (pinfunction "PC13-TAMPER-RTC_2") (pintype "passive+no_connect"))
    )
    (net (code "74") (name "unconnected-(U29-GPA7-Pad28)") (class "Default")
      (node (ref "U29") (pin "28") (pinfunction "GPA7_28") (pintype "passive+no_connect"))
    )
    (net (code "75") (name "unconnected-(U29-GPB3-Pad4)") (class "Default")
      (node (ref "U29") (pin "4") (pinfunction "GPB3_4") (pintype "passive+no_connect"))
    )
    (net (code "76") (name "unconnected-(U29-GPB4-Pad5)") (class "Default")
      (node (ref "U29") (pin "5") (pinfunction "GPB4_5") (pintype "passive+no_connect"))
    )
    (net (code "77") (name "unconnected-(U29-GPB5-Pad6)") (class "Default")
      (node (ref "U29") (pin "6") (pinfunction "GPB5_6") (pintype "passive+no_connect"))
    )
    (net (code "78") (name "unconnected-(U29-GPB6-Pad7)") (class "Default")
      (node (ref "U29") (pin "7") (pinfunction "GPB6_7") (pintype "passive+no_connect"))
    )
    (net (code "79") (name "unconnected-(U29-GPB7-Pad8)") (class "Default")
      (node (ref "U29") (pin "8") (pinfunction "GPB7_8") (pintype "passive+no_connect"))
    )
    (net (code "80") (name "unconnected-(U29-INTA-Pad20)") (class "Default")
      (node (ref "U29") (pin "20") (pinfunction "INTA_20") (pintype "passive+no_connect"))
    )
    (net (code "81") (name "unconnected-(U29-INTB-Pad19)") (class "Default")
      (node (ref "U29") (pin "19") (pinfunction "INTB_19") (pintype "passive+no_connect"))
    )
    (net (code "82") (name "unconnected-(U29-NC-Pad11)") (class "Default")
      (node (ref "U29") (pin "11") (pinfunction "NC_11") (pintype "passive+no_connect"))
    )
    (net (code "83") (name "unconnected-(U29-NC-Pad14)") (class "Default")
      (node (ref "U29") (pin "14") (pinfunction "NC_14") (pintype "passive+no_connect"))
    )
    (net (code "84") (name "unconnected-(U30-GPA7-Pad28)") (class "Default")
      (node (ref "U30") (pin "28") (pinfunction "GPA7_28") (pintype "passive+no_connect"))
    )
    (net (code "85") (name "unconnected-(U30-GPB5-Pad6)") (class "Default")
      (node (ref "U30") (pin "6") (pinfunction "GPB5_6") (pintype "passive+no_connect"))
    )
    (net (code "86") (name "unconnected-(U30-GPB6-Pad7)") (class "Default")
      (node (ref "U30") (pin "7") (pinfunction "GPB6_7") (pintype "passive+no_connect"))
    )
    (net (code "87") (name "unconnected-(U30-GPB7-Pad8)") (class "Default")
      (node (ref "U30") (pin "8") (pinfunction "GPB7_8") (pintype "passive+no_connect"))
    )
    (net (code "88") (name "unconnected-(U30-INTA-Pad20)") (class "Default")
      (node (ref "U30") (pin "20") (pinfunction "INTA_20") (pintype "passive+no_connect"))
    )
    (net (code "89") (name "unconnected-(U30-INTB-Pad19)") (class "Default")
      (node (ref "U30") (pin "19") (pinfunction "INTB_19") (pintype "passive+no_connect"))
    )
    (net (code "90") (name "unconnected-(U30-NC-Pad11)") (class "Default")
      (node (ref "U30") (pin "11") (pinfunction "NC_11") (pintype "passive+no_connect"))
    )
    (net (code "91") (name "unconnected-(U30-NC-Pad14)") (class "Default")
      (node (ref "U30") (pin "14") (pinfunction "NC_14") (pintype "passive+no_connect"))
    )
  )
)
